# Sheet1.net
KiCad netlist of a schematic drawn in Altium Designer
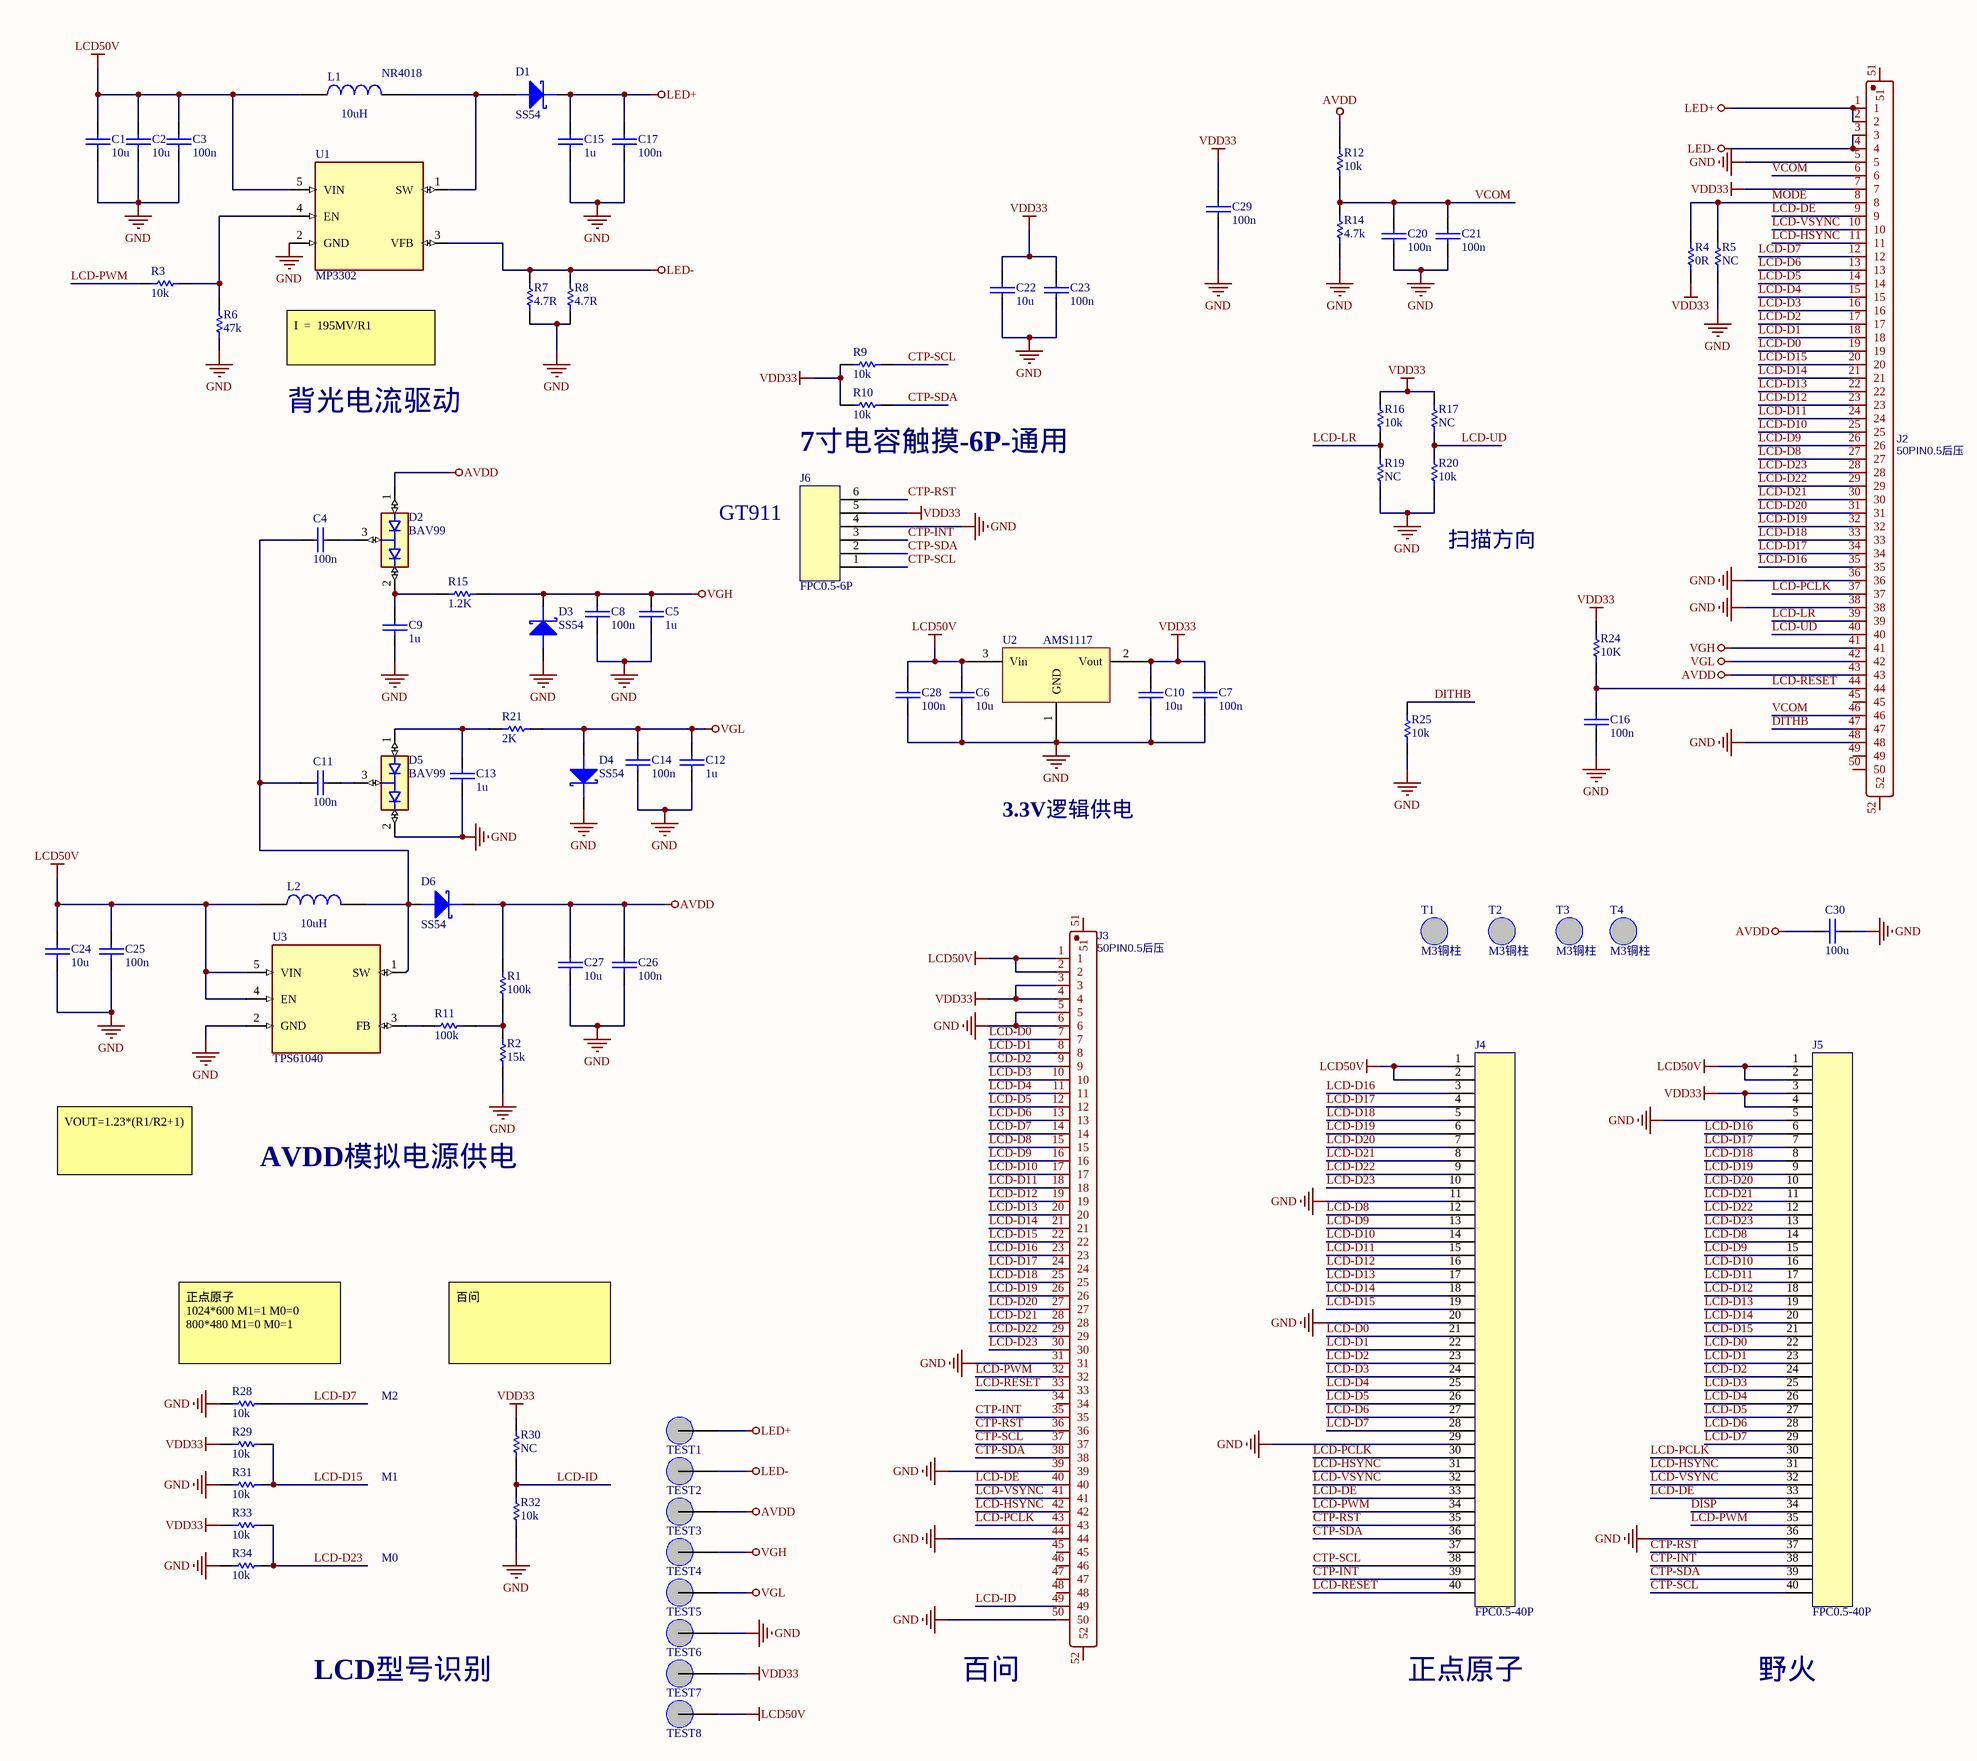
[diagram p0: Sheet1.SchDoc]

(export (version "E")
  (design (tool "Eeschema 10.0.6"))
  (components
    (comp (ref "C1")
      (value "10u")
      (footprint "0603C")
      (description "无极性电容")
      (libsource (lib "常用元件-电容") (part "CAP"))
    )
    (comp (ref "C2")
      (value "10u")
      (footprint "0603C")
      (description "无极性电容")
      (libsource (lib "常用元件-电容") (part "CAP"))
    )
    (comp (ref "C3")
      (value "100n")
      (footprint "0603C")
      (description "无极性电容")
      (libsource (lib "常用元件-电容") (part "CAP"))
    )
    (comp (ref "C4")
      (value "100n")
      (footprint "0603C")
      (description "无极性电容")
      (libsource (lib "常用元件-电容") (part "CAP"))
    )
    (comp (ref "C5")
      (value "1u")
      (footprint "0603C")
      (description "无极性电容")
      (libsource (lib "常用元件-电容") (part "CAP"))
    )
    (comp (ref "C6")
      (value "10u")
      (footprint "0603C")
      (description "无极性电容")
      (libsource (lib "常用元件-电容") (part "CAP"))
    )
    (comp (ref "C7")
      (value "100n")
      (footprint "0603C")
      (description "无极性电容")
      (libsource (lib "常用元件-电容") (part "CAP"))
    )
    (comp (ref "C8")
      (value "100n")
      (footprint "0603C")
      (description "无极性电容")
      (libsource (lib "常用元件-电容") (part "CAP"))
    )
    (comp (ref "C9")
      (value "1u")
      (footprint "0603C")
      (description "无极性电容")
      (libsource (lib "常用元件-电容") (part "CAP"))
    )
    (comp (ref "C10")
      (value "10u")
      (footprint "0603C")
      (description "无极性电容")
      (libsource (lib "常用元件-电容") (part "CAP"))
    )
    (comp (ref "C11")
      (value "100n")
      (footprint "0603C")
      (description "无极性电容")
      (libsource (lib "常用元件-电容") (part "CAP"))
    )
    (comp (ref "C12")
      (value "1u")
      (footprint "0603C")
      (description "无极性电容")
      (libsource (lib "常用元件-电容") (part "CAP"))
    )
    (comp (ref "C13")
      (value "1u")
      (footprint "0603C")
      (description "无极性电容")
      (libsource (lib "常用元件-电容") (part "CAP"))
    )
    (comp (ref "C14")
      (value "100n")
      (footprint "0603C")
      (description "无极性电容")
      (libsource (lib "常用元件-电容") (part "CAP"))
    )
    (comp (ref "C15")
      (value "1u")
      (footprint "0603C")
      (description "无极性电容")
      (libsource (lib "常用元件-电容") (part "CAP"))
    )
    (comp (ref "C16")
      (value "100n")
      (footprint "0603C")
      (description "无极性电容")
      (libsource (lib "常用元件-电容") (part "CAP"))
    )
    (comp (ref "C17")
      (value "100n")
      (footprint "0603C")
      (description "无极性电容")
      (libsource (lib "常用元件-电容") (part "CAP"))
    )
    (comp (ref "C20")
      (value "100n")
      (footprint "0603C")
      (description "无极性电容")
      (libsource (lib "常用元件-电容") (part "CAP"))
    )
    (comp (ref "C21")
      (value "100n")
      (footprint "0603C")
      (description "无极性电容")
      (libsource (lib "常用元件-电容") (part "CAP"))
    )
    (comp (ref "C22")
      (value "10u")
      (footprint "0603C")
      (description "无极性电容")
      (libsource (lib "常用元件-电容") (part "CAP"))
    )
    (comp (ref "C23")
      (value "100n")
      (footprint "0603C")
      (description "无极性电容")
      (libsource (lib "常用元件-电容") (part "CAP"))
    )
    (comp (ref "C24")
      (value "10u")
      (footprint "0603C")
      (description "无极性电容")
      (libsource (lib "常用元件-电容") (part "CAP"))
    )
    (comp (ref "C25")
      (value "100n")
      (footprint "0603C")
      (description "无极性电容")
      (libsource (lib "常用元件-电容") (part "CAP"))
    )
    (comp (ref "C26")
      (value "100n")
      (footprint "0603C")
      (description "无极性电容")
      (libsource (lib "常用元件-电容") (part "CAP"))
    )
    (comp (ref "C27")
      (value "10u")
      (footprint "0603C")
      (description "无极性电容")
      (libsource (lib "常用元件-电容") (part "CAP"))
    )
    (comp (ref "C28")
      (value "100n")
      (footprint "0603C")
      (description "无极性电容")
      (libsource (lib "常用元件-电容") (part "CAP"))
    )
    (comp (ref "C29")
      (value "100n")
      (footprint "0603C")
      (description "无极性电容")
      (libsource (lib "常用元件-电容") (part "CAP"))
    )
    (comp (ref "C30")
      (value "100u")
      (footprint "0603C")
      (description "无极性电容")
      (libsource (lib "常用元件-电容") (part "CAP"))
    )
    (comp (ref "D1")
      (value "SS54")
      (footprint "SOD-123")
      (description "肖特基二极管")
      (libsource (lib "常用元件-二极管") (part "DIODE SCHOTTKY"))
    )
    (comp (ref "D2")
      (value "BAV99")
      (footprint "BAV99:SOT23-3")
      (fields (field (name "MF") "{'manufacturer': u'ON Semiconductor'}"))
      (libsource (lib "*") (part "BAV99"))
    )
    (comp (ref "D3")
      (value "SS54")
      (footprint "SOD-123")
      (description "肖特基二极管")
      (libsource (lib "常用元件-二极管") (part "DIODE SCHOTTKY"))
    )
    (comp (ref "D4")
      (value "SS54")
      (footprint "SOD-123")
      (description "肖特基二极管")
      (libsource (lib "常用元件-二极管") (part "DIODE SCHOTTKY"))
    )
    (comp (ref "D5")
      (value "BAV99")
      (footprint "BAV99:SOT23-3")
      (fields (field (name "MF") "{'manufacturer': u'ON Semiconductor'}"))
      (libsource (lib "*") (part "BAV99"))
    )
    (comp (ref "D6")
      (value "SS54")
      (footprint "SOD-123")
      (description "肖特基二极管")
      (libsource (lib "常用元件-二极管") (part "DIODE SCHOTTKY"))
    )
    (comp (ref "J2")
      (value "50PIN0.5后压")
      (footprint "FPC-SMD_KH-FG0.5-H2.0-50PIN")
      (fields (field (name "BOM_SUPPLIER PART") "C9900011403") (field (name "CONTRIBUTOR") "LCSC"))
      (libsource (lib "altium-import") (part "root_0_50PIN0.5后压_"))
    )
    (comp (ref "J3")
      (value "50PIN0.5后压")
      (footprint "FPC-SMD_KH-FG0.5-H2.0-50PIN")
      (fields (field (name "BOM_SUPPLIER PART") "C9900011403") (field (name "CONTRIBUTOR") "LCSC"))
      (libsource (lib "altium-import") (part "root_0_50PIN0.5后压_"))
    )
    (comp (ref "J4")
      (value "FPC0.5-40P")
      (footprint "FPC0.5-40P")
      (description "贴片")
      (libsource (lib "插接类-FPC") (part "FPC0.5-40P"))
    )
    (comp (ref "J5")
      (value "FPC0.5-40P")
      (footprint "FPC0.5-40P")
      (description "贴片")
      (libsource (lib "插接类-FPC") (part "FPC0.5-40P"))
    )
    (comp (ref "J6")
      (value "FPC0.5-6P")
      (footprint "FPC0.5-6P")
      (description "贴片")
      (libsource (lib "插接类-FPC") (part "FPC0.5-6P"))
    )
    (comp (ref "L1")
      (value "10uH")
      (footprint "CD42")
      (description "INDUCTOR")
      (libsource (lib "常用元件-电感") (part "INDUCTOR"))
    )
    (comp (ref "L2")
      (value "10uH")
      (footprint "CD42")
      (description "INDUCTOR")
      (libsource (lib "常用元件-电感") (part "INDUCTOR"))
    )
    (comp (ref "R1") (value "100k") (footprint "0603R") (libsource (lib "常用元件-电阻") (part "RES")))
    (comp (ref "R2") (value "15k") (footprint "0603R") (libsource (lib "常用元件-电阻") (part "RES")))
    (comp (ref "R3") (value "10k") (footprint "0603R") (libsource (lib "常用元件-电阻") (part "RES")))
    (comp (ref "R4") (value "0R") (footprint "0603R") (libsource (lib "常用元件-电阻") (part "RES")))
    (comp (ref "R5") (value "NC") (footprint "0603R") (libsource (lib "常用元件-电阻") (part "RES")))
    (comp (ref "R6") (value "47k") (footprint "0603R") (libsource (lib "常用元件-电阻") (part "RES")))
    (comp (ref "R7") (value "4.7R") (footprint "0603R") (libsource (lib "常用元件-电阻") (part "RES")))
    (comp (ref "R8") (value "4.7R") (footprint "0603R") (libsource (lib "常用元件-电阻") (part "RES")))
    (comp (ref "R9") (value "10k") (footprint "0603R") (libsource (lib "常用元件-电阻") (part "RES")))
    (comp (ref "R10") (value "10k") (footprint "0603R") (libsource (lib "常用元件-电阻") (part "RES")))
    (comp (ref "R11") (value "100k") (footprint "0603R") (libsource (lib "常用元件-电阻") (part "RES")))
    (comp (ref "R12") (value "10k") (footprint "0603R") (libsource (lib "常用元件-电阻") (part "RES")))
    (comp (ref "R14") (value "4.7k") (footprint "0603R") (libsource (lib "常用元件-电阻") (part "RES")))
    (comp (ref "R15") (value "1.2K") (footprint "0603R") (libsource (lib "常用元件-电阻") (part "RES")))
    (comp (ref "R16") (value "10k") (footprint "0603R") (libsource (lib "常用元件-电阻") (part "RES")))
    (comp (ref "R17") (value "NC") (footprint "0603R") (libsource (lib "常用元件-电阻") (part "RES")))
    (comp (ref "R19") (value "NC") (footprint "0603R") (libsource (lib "常用元件-电阻") (part "RES")))
    (comp (ref "R20") (value "10k") (footprint "0603R") (libsource (lib "常用元件-电阻") (part "RES")))
    (comp (ref "R21") (value "2K") (footprint "0603R") (libsource (lib "常用元件-电阻") (part "RES")))
    (comp (ref "R24") (value "10K") (footprint "0603R") (libsource (lib "常用元件-电阻") (part "RES")))
    (comp (ref "R25") (value "10k") (footprint "0603R") (libsource (lib "常用元件-电阻") (part "RES")))
    (comp (ref "R28") (value "10k") (footprint "0603R") (libsource (lib "常用元件-电阻") (part "RES")))
    (comp (ref "R29") (value "10k") (footprint "0603R") (libsource (lib "常用元件-电阻") (part "RES")))
    (comp (ref "R30") (value "NC") (footprint "0603R") (libsource (lib "常用元件-电阻") (part "RES")))
    (comp (ref "R31") (value "10k") (footprint "0603R") (libsource (lib "常用元件-电阻") (part "RES")))
    (comp (ref "R32") (value "10k") (footprint "0603R") (libsource (lib "常用元件-电阻") (part "RES")))
    (comp (ref "R33") (value "10k") (footprint "0603R") (libsource (lib "常用元件-电阻") (part "RES")))
    (comp (ref "R34") (value "10k") (footprint "0603R") (libsource (lib "常用元件-电阻") (part "RES")))
    (comp (ref "T1") (value "M3铜柱") (footprint "M3 单孔") (libsource (lib "M3铜柱") (part "M3铜柱")))
    (comp (ref "T2") (value "M3铜柱") (footprint "M3 单孔") (libsource (lib "M3铜柱") (part "M3铜柱")))
    (comp (ref "T3") (value "M3铜柱") (footprint "M3 单孔") (libsource (lib "M3铜柱") (part "M3铜柱")))
    (comp (ref "T4") (value "M3铜柱") (footprint "M3 单孔") (libsource (lib "M3铜柱") (part "M3铜柱")))
    (comp (ref "TEST1")
      (value "TEST")
      (footprint "TEST SMALL")
      (description "测试针")
      (fields (field (name "版权归属") "源创客"))
      (libsource (lib "测试类-测试针") (part "TEST"))
    )
    (comp (ref "TEST2")
      (value "TEST")
      (footprint "TEST SMALL")
      (description "测试针")
      (fields (field (name "版权归属") "源创客"))
      (libsource (lib "测试类-测试针") (part "TEST"))
    )
    (comp (ref "TEST3")
      (value "TEST")
      (footprint "TEST SMALL")
      (description "测试针")
      (fields (field (name "版权归属") "源创客"))
      (libsource (lib "测试类-测试针") (part "TEST"))
    )
    (comp (ref "TEST4")
      (value "TEST")
      (footprint "TEST SMALL")
      (description "测试针")
      (fields (field (name "版权归属") "源创客"))
      (libsource (lib "测试类-测试针") (part "TEST"))
    )
    (comp (ref "TEST5")
      (value "TEST")
      (footprint "TEST SMALL")
      (description "测试针")
      (fields (field (name "版权归属") "源创客"))
      (libsource (lib "测试类-测试针") (part "TEST"))
    )
    (comp (ref "TEST6")
      (value "TEST")
      (footprint "TEST SMALL")
      (description "测试针")
      (fields (field (name "版权归属") "源创客"))
      (libsource (lib "测试类-测试针") (part "TEST"))
    )
    (comp (ref "TEST7")
      (value "TEST")
      (footprint "TEST SMALL")
      (description "测试针")
      (fields (field (name "版权归属") "源创客"))
      (libsource (lib "测试类-测试针") (part "TEST"))
    )
    (comp (ref "TEST8")
      (value "TEST")
      (footprint "TEST SMALL")
      (description "测试针")
      (fields (field (name "版权归属") "源创客"))
      (libsource (lib "测试类-测试针") (part "TEST"))
    )
    (comp (ref "U1")
      (value "MP3302")
      (footprint "SOT95P280X100-5N")
      (fields
        (field (name "MP") "TPS563201DDCR")
        (field (name "MF") "{'manufacturer': u'Texas Instruments'}")
      )
      (libsource (lib "MP3302") (part "MP3302"))
    )
    (comp (ref "U2")
      (value "AMS1117")
      (footprint "SOT223")
      (description "三端稳压芯片")
      (libsource (lib "芯片-电源芯片") (part "AMS1117"))
    )
    (comp (ref "U3")
      (value "TPS61040")
      (footprint "SOT95P280X100-5N")
      (fields
        (field (name "MP") "TPS563201DDCR")
        (field (name "MF") "{'manufacturer': u'Texas Instruments'}")
      )
      (libsource (lib "MP1541") (part "MP1541"))
    )
  )
  (nets
    (net (code "1") (name "/CTP-INT") (class "Default")
      (node (ref "J3") (pin "35") (pinfunction "35_35") (pintype "passive"))
      (node (ref "J4") (pin "39") (pinfunction "39_39") (pintype "passive"))
      (node (ref "J5") (pin "38") (pinfunction "38_38") (pintype "passive"))
      (node (ref "J6") (pin "3") (pinfunction "3_3") (pintype "passive"))
    )
    (net (code "2") (name "/CTP-RST") (class "Default")
      (node (ref "J3") (pin "36") (pinfunction "36_36") (pintype "passive"))
      (node (ref "J4") (pin "35") (pinfunction "35_35") (pintype "passive"))
      (node (ref "J5") (pin "37") (pinfunction "37_37") (pintype "passive"))
      (node (ref "J6") (pin "6") (pinfunction "6_6") (pintype "passive"))
    )
    (net (code "3") (name "/CTP-SCL") (class "Default")
      (node (ref "J3") (pin "37") (pinfunction "37_37") (pintype "passive"))
      (node (ref "J4") (pin "38") (pinfunction "38_38") (pintype "passive"))
      (node (ref "J5") (pin "40") (pinfunction "40_40") (pintype "passive"))
      (node (ref "J6") (pin "1") (pinfunction "1_1") (pintype "passive"))
      (node (ref "R9") (pin "1") (pinfunction "1_1") (pintype "passive"))
    )
    (net (code "4") (name "/CTP-SDA") (class "Default")
      (node (ref "J3") (pin "38") (pinfunction "38_38") (pintype "passive"))
      (node (ref "J4") (pin "36") (pinfunction "36_36") (pintype "passive"))
      (node (ref "J5") (pin "39") (pinfunction "39_39") (pintype "passive"))
      (node (ref "J6") (pin "2") (pinfunction "2_2") (pintype "passive"))
      (node (ref "R10") (pin "1") (pinfunction "1_1") (pintype "passive"))
    )
    (net (code "5") (name "/DISP") (class "Default")
      (node (ref "J5") (pin "34") (pinfunction "34_34") (pintype "passive"))
    )
    (net (code "6") (name "/DITHB") (class "Default")
      (node (ref "J2") (pin "47") (pinfunction "47_47") (pintype "passive"))
      (node (ref "R25") (pin "1") (pinfunction "1_1") (pintype "passive"))
    )
    (net (code "7") (name "/LCD-D0") (class "Default")
      (node (ref "J2") (pin "19") (pinfunction "19_19") (pintype "passive"))
      (node (ref "J3") (pin "7") (pinfunction "7_7") (pintype "passive"))
      (node (ref "J4") (pin "21") (pinfunction "21_21") (pintype "passive"))
      (node (ref "J5") (pin "22") (pinfunction "22_22") (pintype "passive"))
    )
    (net (code "8") (name "/LCD-D1") (class "Default")
      (node (ref "J2") (pin "18") (pinfunction "18_18") (pintype "passive"))
      (node (ref "J3") (pin "8") (pinfunction "8_8") (pintype "passive"))
      (node (ref "J4") (pin "22") (pinfunction "22_22") (pintype "passive"))
      (node (ref "J5") (pin "23") (pinfunction "23_23") (pintype "passive"))
    )
    (net (code "9") (name "/LCD-D2") (class "Default")
      (node (ref "J2") (pin "17") (pinfunction "17_17") (pintype "passive"))
      (node (ref "J3") (pin "9") (pinfunction "9_9") (pintype "passive"))
      (node (ref "J4") (pin "23") (pinfunction "23_23") (pintype "passive"))
      (node (ref "J5") (pin "24") (pinfunction "24_24") (pintype "passive"))
    )
    (net (code "10") (name "/LCD-D3") (class "Default")
      (node (ref "J2") (pin "16") (pinfunction "16_16") (pintype "passive"))
      (node (ref "J3") (pin "10") (pinfunction "10_10") (pintype "passive"))
      (node (ref "J4") (pin "24") (pinfunction "24_24") (pintype "passive"))
      (node (ref "J5") (pin "25") (pinfunction "25_25") (pintype "passive"))
    )
    (net (code "11") (name "/LCD-D4") (class "Default")
      (node (ref "J2") (pin "15") (pinfunction "15_15") (pintype "passive"))
      (node (ref "J3") (pin "11") (pinfunction "11_11") (pintype "passive"))
      (node (ref "J4") (pin "25") (pinfunction "25_25") (pintype "passive"))
      (node (ref "J5") (pin "26") (pinfunction "26_26") (pintype "passive"))
    )
    (net (code "12") (name "/LCD-D5") (class "Default")
      (node (ref "J2") (pin "14") (pinfunction "14_14") (pintype "passive"))
      (node (ref "J3") (pin "12") (pinfunction "12_12") (pintype "passive"))
      (node (ref "J4") (pin "26") (pinfunction "26_26") (pintype "passive"))
      (node (ref "J5") (pin "27") (pinfunction "27_27") (pintype "passive"))
    )
    (net (code "13") (name "/LCD-D6") (class "Default")
      (node (ref "J2") (pin "13") (pinfunction "13_13") (pintype "passive"))
      (node (ref "J3") (pin "13") (pinfunction "13_13") (pintype "passive"))
      (node (ref "J4") (pin "27") (pinfunction "27_27") (pintype "passive"))
      (node (ref "J5") (pin "28") (pinfunction "28_28") (pintype "passive"))
    )
    (net (code "14") (name "/LCD-D7") (class "Default")
      (node (ref "J2") (pin "12") (pinfunction "12_12") (pintype "passive"))
      (node (ref "J3") (pin "14") (pinfunction "14_14") (pintype "passive"))
      (node (ref "J4") (pin "28") (pinfunction "28_28") (pintype "passive"))
      (node (ref "J5") (pin "29") (pinfunction "29_29") (pintype "passive"))
      (node (ref "R28") (pin "2") (pinfunction "2_2") (pintype "passive"))
    )
    (net (code "15") (name "/LCD-D8") (class "Default")
      (node (ref "J2") (pin "27") (pinfunction "27_27") (pintype "passive"))
      (node (ref "J3") (pin "15") (pinfunction "15_15") (pintype "passive"))
      (node (ref "J4") (pin "12") (pinfunction "12_12") (pintype "passive"))
      (node (ref "J5") (pin "14") (pinfunction "14_14") (pintype "passive"))
    )
    (net (code "16") (name "/LCD-D9") (class "Default")
      (node (ref "J2") (pin "26") (pinfunction "26_26") (pintype "passive"))
      (node (ref "J3") (pin "16") (pinfunction "16_16") (pintype "passive"))
      (node (ref "J4") (pin "13") (pinfunction "13_13") (pintype "passive"))
      (node (ref "J5") (pin "15") (pinfunction "15_15") (pintype "passive"))
    )
    (net (code "17") (name "/LCD-D10") (class "Default")
      (node (ref "J2") (pin "25") (pinfunction "25_25") (pintype "passive"))
      (node (ref "J3") (pin "17") (pinfunction "17_17") (pintype "passive"))
      (node (ref "J4") (pin "14") (pinfunction "14_14") (pintype "passive"))
      (node (ref "J5") (pin "16") (pinfunction "16_16") (pintype "passive"))
    )
    (net (code "18") (name "/LCD-D11") (class "Default")
      (node (ref "J2") (pin "24") (pinfunction "24_24") (pintype "passive"))
      (node (ref "J3") (pin "18") (pinfunction "18_18") (pintype "passive"))
      (node (ref "J4") (pin "15") (pinfunction "15_15") (pintype "passive"))
      (node (ref "J5") (pin "17") (pinfunction "17_17") (pintype "passive"))
    )
    (net (code "19") (name "/LCD-D12") (class "Default")
      (node (ref "J2") (pin "23") (pinfunction "23_23") (pintype "passive"))
      (node (ref "J3") (pin "19") (pinfunction "19_19") (pintype "passive"))
      (node (ref "J4") (pin "16") (pinfunction "16_16") (pintype "passive"))
      (node (ref "J5") (pin "18") (pinfunction "18_18") (pintype "passive"))
    )
    (net (code "20") (name "/LCD-D13") (class "Default")
      (node (ref "J2") (pin "22") (pinfunction "22_22") (pintype "passive"))
      (node (ref "J3") (pin "20") (pinfunction "20_20") (pintype "passive"))
      (node (ref "J4") (pin "17") (pinfunction "17_17") (pintype "passive"))
      (node (ref "J5") (pin "19") (pinfunction "19_19") (pintype "passive"))
    )
    (net (code "21") (name "/LCD-D14") (class "Default")
      (node (ref "J2") (pin "21") (pinfunction "21_21") (pintype "passive"))
      (node (ref "J3") (pin "21") (pinfunction "21_21") (pintype "passive"))
      (node (ref "J4") (pin "18") (pinfunction "18_18") (pintype "passive"))
      (node (ref "J5") (pin "20") (pinfunction "20_20") (pintype "passive"))
    )
    (net (code "22") (name "/LCD-D15") (class "Default")
      (node (ref "J2") (pin "20") (pinfunction "20_20") (pintype "passive"))
      (node (ref "J3") (pin "22") (pinfunction "22_22") (pintype "passive"))
      (node (ref "J4") (pin "19") (pinfunction "19_19") (pintype "passive"))
      (node (ref "J5") (pin "21") (pinfunction "21_21") (pintype "passive"))
      (node (ref "R29") (pin "2") (pinfunction "2_2") (pintype "passive"))
      (node (ref "R31") (pin "1") (pinfunction "1_1") (pintype "passive"))
    )
    (net (code "23") (name "/LCD-D16") (class "Default")
      (node (ref "J2") (pin "35") (pinfunction "35_35") (pintype "passive"))
      (node (ref "J3") (pin "23") (pinfunction "23_23") (pintype "passive"))
      (node (ref "J4") (pin "3") (pinfunction "3_3") (pintype "passive"))
      (node (ref "J5") (pin "6") (pinfunction "6_6") (pintype "passive"))
    )
    (net (code "24") (name "/LCD-D17") (class "Default")
      (node (ref "J2") (pin "34") (pinfunction "34_34") (pintype "passive"))
      (node (ref "J3") (pin "24") (pinfunction "24_24") (pintype "passive"))
      (node (ref "J4") (pin "4") (pinfunction "4_4") (pintype "passive"))
      (node (ref "J5") (pin "7") (pinfunction "7_7") (pintype "passive"))
    )
    (net (code "25") (name "/LCD-D18") (class "Default")
      (node (ref "J2") (pin "33") (pinfunction "33_33") (pintype "passive"))
      (node (ref "J3") (pin "25") (pinfunction "25_25") (pintype "passive"))
      (node (ref "J4") (pin "5") (pinfunction "5_5") (pintype "passive"))
      (node (ref "J5") (pin "8") (pinfunction "8_8") (pintype "passive"))
    )
    (net (code "26") (name "/LCD-D19") (class "Default")
      (node (ref "J2") (pin "32") (pinfunction "32_32") (pintype "passive"))
      (node (ref "J3") (pin "26") (pinfunction "26_26") (pintype "passive"))
      (node (ref "J4") (pin "6") (pinfunction "6_6") (pintype "passive"))
      (node (ref "J5") (pin "9") (pinfunction "9_9") (pintype "passive"))
    )
    (net (code "27") (name "/LCD-D20") (class "Default")
      (node (ref "J2") (pin "31") (pinfunction "31_31") (pintype "passive"))
      (node (ref "J3") (pin "27") (pinfunction "27_27") (pintype "passive"))
      (node (ref "J4") (pin "7") (pinfunction "7_7") (pintype "passive"))
      (node (ref "J5") (pin "10") (pinfunction "10_10") (pintype "passive"))
    )
    (net (code "28") (name "/LCD-D21") (class "Default")
      (node (ref "J2") (pin "30") (pinfunction "30_30") (pintype "passive"))
      (node (ref "J3") (pin "28") (pinfunction "28_28") (pintype "passive"))
      (node (ref "J4") (pin "8") (pinfunction "8_8") (pintype "passive"))
      (node (ref "J5") (pin "11") (pinfunction "11_11") (pintype "passive"))
    )
    (net (code "29") (name "/LCD-D22") (class "Default")
      (node (ref "J2") (pin "29") (pinfunction "29_29") (pintype "passive"))
      (node (ref "J3") (pin "29") (pinfunction "29_29") (pintype "passive"))
      (node (ref "J4") (pin "9") (pinfunction "9_9") (pintype "passive"))
      (node (ref "J5") (pin "12") (pinfunction "12_12") (pintype "passive"))
    )
    (net (code "30") (name "/LCD-D23") (class "Default")
      (node (ref "J2") (pin "28") (pinfunction "28_28") (pintype "passive"))
      (node (ref "J3") (pin "30") (pinfunction "30_30") (pintype "passive"))
      (node (ref "J4") (pin "10") (pinfunction "10_10") (pintype "passive"))
      (node (ref "J5") (pin "13") (pinfunction "13_13") (pintype "passive"))
      (node (ref "R33") (pin "2") (pinfunction "2_2") (pintype "passive"))
      (node (ref "R34") (pin "1") (pinfunction "1_1") (pintype "passive"))
    )
    (net (code "31") (name "/LCD-DE") (class "Default")
      (node (ref "J2") (pin "9") (pinfunction "9_9") (pintype "passive"))
      (node (ref "J3") (pin "40") (pinfunction "40_40") (pintype "passive"))
      (node (ref "J4") (pin "33") (pinfunction "33_33") (pintype "passive"))
      (node (ref "J5") (pin "33") (pinfunction "33_33") (pintype "passive"))
    )
    (net (code "32") (name "/LCD-HSYNC") (class "Default")
      (node (ref "J2") (pin "11") (pinfunction "11_11") (pintype "passive"))
      (node (ref "J3") (pin "42") (pinfunction "42_42") (pintype "passive"))
      (node (ref "J4") (pin "31") (pinfunction "31_31") (pintype "passive"))
      (node (ref "J5") (pin "31") (pinfunction "31_31") (pintype "passive"))
    )
    (net (code "33") (name "/LCD-ID") (class "Default")
      (node (ref "J3") (pin "49") (pinfunction "49_49") (pintype "passive"))
      (node (ref "R30") (pin "2") (pinfunction "2_2") (pintype "passive"))
      (node (ref "R32") (pin "2") (pinfunction "2_2") (pintype "passive"))
    )
    (net (code "34") (name "/LCD-LR") (class "Default")
      (node (ref "J2") (pin "39") (pinfunction "39_39") (pintype "passive"))
      (node (ref "R16") (pin "2") (pinfunction "2_2") (pintype "passive"))
      (node (ref "R19") (pin "1") (pinfunction "1_1") (pintype "passive"))
    )
    (net (code "35") (name "/LCD-PCLK") (class "Default")
      (node (ref "J2") (pin "37") (pinfunction "37_37") (pintype "passive"))
      (node (ref "J3") (pin "43") (pinfunction "43_43") (pintype "passive"))
      (node (ref "J4") (pin "30") (pinfunction "30_30") (pintype "passive"))
      (node (ref "J5") (pin "30") (pinfunction "30_30") (pintype "passive"))
    )
    (net (code "36") (name "/LCD-PWM") (class "Default")
      (node (ref "J3") (pin "32") (pinfunction "32_32") (pintype "passive"))
      (node (ref "J4") (pin "34") (pinfunction "34_34") (pintype "passive"))
      (node (ref "J5") (pin "35") (pinfunction "35_35") (pintype "passive"))
      (node (ref "R3") (pin "1") (pinfunction "1_1") (pintype "passive"))
    )
    (net (code "37") (name "/LCD-RESET") (class "Default")
      (node (ref "C16") (pin "2") (pinfunction "2_2") (pintype "passive"))
      (node (ref "J2") (pin "44") (pinfunction "44_44") (pintype "passive"))
      (node (ref "J3") (pin "33") (pinfunction "33_33") (pintype "passive"))
      (node (ref "J4") (pin "40") (pinfunction "40_40") (pintype "passive"))
      (node (ref "R24") (pin "2") (pinfunction "2_2") (pintype "passive"))
    )
    (net (code "38") (name "/LCD-UD") (class "Default")
      (node (ref "J2") (pin "40") (pinfunction "40_40") (pintype "passive"))
      (node (ref "R17") (pin "2") (pinfunction "2_2") (pintype "passive"))
      (node (ref "R20") (pin "1") (pinfunction "1_1") (pintype "passive"))
    )
    (net (code "39") (name "/LCD-VSYNC") (class "Default")
      (node (ref "J2") (pin "10") (pinfunction "10_10") (pintype "passive"))
      (node (ref "J3") (pin "41") (pinfunction "41_41") (pintype "passive"))
      (node (ref "J4") (pin "32") (pinfunction "32_32") (pintype "passive"))
      (node (ref "J5") (pin "32") (pinfunction "32_32") (pintype "passive"))
    )
    (net (code "40") (name "/MODE") (class "Default")
      (node (ref "J2") (pin "8") (pinfunction "8_8") (pintype "passive"))
      (node (ref "R4") (pin "1") (pinfunction "1_1") (pintype "passive"))
      (node (ref "R5") (pin "1") (pinfunction "1_1") (pintype "passive"))
    )
    (net (code "41") (name "/VCOM") (class "Default")
      (node (ref "C20") (pin "2") (pinfunction "2_2") (pintype "passive"))
      (node (ref "C21") (pin "2") (pinfunction "2_2") (pintype "passive"))
      (node (ref "J2") (pin "46") (pinfunction "46_46") (pintype "passive"))
      (node (ref "J2") (pin "6") (pinfunction "6_6") (pintype "passive"))
      (node (ref "R12") (pin "2") (pinfunction "2_2") (pintype "passive"))
      (node (ref "R14") (pin "1") (pinfunction "1_1") (pintype "passive"))
    )
    (net (code "42") (name "AVDD") (class "Default")
      (node (ref "C26") (pin "2") (pinfunction "2_2") (pintype "passive"))
      (node (ref "C27") (pin "2") (pinfunction "2_2") (pintype "passive"))
      (node (ref "C30") (pin "1") (pinfunction "1_1") (pintype "passive"))
      (node (ref "D2") (pin "1") (pinfunction "A1_1") (pintype "bidirectional"))
      (node (ref "D6") (pin "K") (pinfunction "K_K") (pintype "passive"))
      (node (ref "J2") (pin "43") (pinfunction "43_43") (pintype "passive"))
      (node (ref "R1") (pin "1") (pinfunction "1_1") (pintype "passive"))
      (node (ref "R12") (pin "1") (pinfunction "1_1") (pintype "passive"))
      (node (ref "TEST3") (pin "1") (pinfunction "1_1") (pintype "passive"))
    )
    (net (code "43") (name "GND") (class "Default")
      (node (ref "C1") (pin "1") (pinfunction "1_1") (pintype "passive"))
      (node (ref "C10") (pin "1") (pinfunction "1_1") (pintype "passive"))
      (node (ref "C12") (pin "1") (pinfunction "1_1") (pintype "passive"))
      (node (ref "C13") (pin "2") (pinfunction "2_2") (pintype "passive"))
      (node (ref "C14") (pin "1") (pinfunction "1_1") (pintype "passive"))
      (node (ref "C15") (pin "1") (pinfunction "1_1") (pintype "passive"))
      (node (ref "C16") (pin "1") (pinfunction "1_1") (pintype "passive"))
      (node (ref "C17") (pin "1") (pinfunction "1_1") (pintype "passive"))
      (node (ref "C2") (pin "1") (pinfunction "1_1") (pintype "passive"))
      (node (ref "C20") (pin "1") (pinfunction "1_1") (pintype "passive"))
      (node (ref "C21") (pin "1") (pinfunction "1_1") (pintype "passive"))
      (node (ref "C22") (pin "1") (pinfunction "1_1") (pintype "passive"))
      (node (ref "C23") (pin "1") (pinfunction "1_1") (pintype "passive"))
      (node (ref "C24") (pin "1") (pinfunction "1_1") (pintype "passive"))
      (node (ref "C25") (pin "1") (pinfunction "1_1") (pintype "passive"))
      (node (ref "C26") (pin "1") (pinfunction "1_1") (pintype "passive"))
      (node (ref "C27") (pin "1") (pinfunction "1_1") (pintype "passive"))
      (node (ref "C28") (pin "1") (pinfunction "1_1") (pintype "passive"))
      (node (ref "C29") (pin "1") (pinfunction "1_1") (pintype "passive"))
      (node (ref "C3") (pin "1") (pinfunction "1_1") (pintype "passive"))
      (node (ref "C30") (pin "2") (pinfunction "2_2") (pintype "passive"))
      (node (ref "C5") (pin "1") (pinfunction "1_1") (pintype "passive"))
      (node (ref "C6") (pin "1") (pinfunction "1_1") (pintype "passive"))
      (node (ref "C7") (pin "1") (pinfunction "1_1") (pintype "passive"))
      (node (ref "C8") (pin "1") (pinfunction "1_1") (pintype "passive"))
      (node (ref "C9") (pin "1") (pinfunction "1_1") (pintype "passive"))
      (node (ref "D3") (pin "A") (pinfunction "A_A") (pintype "passive"))
      (node (ref "D4") (pin "K") (pinfunction "K_K") (pintype "passive"))
      (node (ref "D5") (pin "2") (pinfunction "C2_2") (pintype "bidirectional"))
      (node (ref "J2") (pin "36") (pinfunction "36_36") (pintype "passive"))
      (node (ref "J2") (pin "38") (pinfunction "38_38") (pintype "passive"))
      (node (ref "J2") (pin "48") (pinfunction "48_48") (pintype "passive"))
      (node (ref "J2") (pin "5") (pinfunction "5_5") (pintype "passive"))
      (node (ref "J3") (pin "31") (pinfunction "31_31") (pintype "passive"))
      (node (ref "J3") (pin "39") (pinfunction "39_39") (pintype "passive"))
      (node (ref "J3") (pin "44") (pinfunction "44_44") (pintype "passive"))
      (node (ref "J3") (pin "5") (pinfunction "5_5") (pintype "passive"))
      (node (ref "J3") (pin "50") (pinfunction "50_50") (pintype "passive"))
      (node (ref "J3") (pin "6") (pinfunction "6_6") (pintype "passive"))
      (node (ref "J4") (pin "11") (pinfunction "11_11") (pintype "passive"))
      (node (ref "J4") (pin "20") (pinfunction "20_20") (pintype "passive"))
      (node (ref "J4") (pin "29") (pinfunction "29_29") (pintype "passive"))
      (node (ref "J5") (pin "36") (pinfunction "36_36") (pintype "passive"))
      (node (ref "J5") (pin "5") (pinfunction "5_5") (pintype "passive"))
      (node (ref "J6") (pin "4") (pinfunction "4_4") (pintype "passive"))
      (node (ref "R14") (pin "2") (pinfunction "2_2") (pintype "passive"))
      (node (ref "R19") (pin "2") (pinfunction "2_2") (pintype "passive"))
      (node (ref "R2") (pin "1") (pinfunction "1_1") (pintype "passive"))
      (node (ref "R20") (pin "2") (pinfunction "2_2") (pintype "passive"))
      (node (ref "R25") (pin "2") (pinfunction "2_2") (pintype "passive"))
      (node (ref "R28") (pin "1") (pinfunction "1_1") (pintype "passive"))
      (node (ref "R31") (pin "2") (pinfunction "2_2") (pintype "passive"))
      (node (ref "R32") (pin "1") (pinfunction "1_1") (pintype "passive"))
      (node (ref "R34") (pin "2") (pinfunction "2_2") (pintype "passive"))
      (node (ref "R5") (pin "2") (pinfunction "2_2") (pintype "passive"))
      (node (ref "R6") (pin "1") (pinfunction "1_1") (pintype "passive"))
      (node (ref "R7") (pin "1") (pinfunction "1_1") (pintype "passive"))
      (node (ref "R8") (pin "1") (pinfunction "1_1") (pintype "passive"))
      (node (ref "TEST6") (pin "1") (pinfunction "1_1") (pintype "passive"))
      (node (ref "U1") (pin "2") (pinfunction "GND_2") (pintype "input"))
      (node (ref "U2") (pin "1") (pinfunction "GND_1") (pintype "passive"))
      (node (ref "U3") (pin "2") (pinfunction "GND_2") (pintype "input"))
    )
    (net (code "44") (name "LCD50V") (class "Default")
      (node (ref "C1") (pin "2") (pinfunction "2_2") (pintype "passive"))
      (node (ref "C2") (pin "2") (pinfunction "2_2") (pintype "passive"))
      (node (ref "C24") (pin "2") (pinfunction "2_2") (pintype "passive"))
      (node (ref "C25") (pin "2") (pinfunction "2_2") (pintype "passive"))
      (node (ref "C28") (pin "2") (pinfunction "2_2") (pintype "passive"))
      (node (ref "C3") (pin "2") (pinfunction "2_2") (pintype "passive"))
      (node (ref "C6") (pin "2") (pinfunction "2_2") (pintype "passive"))
      (node (ref "J3") (pin "1") (pinfunction "1_1") (pintype "passive"))
      (node (ref "J3") (pin "2") (pinfunction "2_2") (pintype "passive"))
      (node (ref "J4") (pin "1") (pinfunction "1_1") (pintype "passive"))
      (node (ref "J4") (pin "2") (pinfunction "2_2") (pintype "passive"))
      (node (ref "J5") (pin "1") (pinfunction "1_1") (pintype "passive"))
      (node (ref "J5") (pin "2") (pinfunction "2_2") (pintype "passive"))
      (node (ref "L1") (pin "1") (pinfunction "1_1") (pintype "passive"))
      (node (ref "L2") (pin "1") (pinfunction "1_1") (pintype "passive"))
      (node (ref "TEST8") (pin "1") (pinfunction "1_1") (pintype "passive"))
      (node (ref "U1") (pin "5") (pinfunction "VIN_5") (pintype "input"))
      (node (ref "U2") (pin "3") (pinfunction "Vin_3") (pintype "passive"))
      (node (ref "U3") (pin "4") (pinfunction "EN_4") (pintype "input"))
      (node (ref "U3") (pin "5") (pinfunction "VIN_5") (pintype "input"))
    )
    (net (code "45") (name "LED+") (class "Default")
      (node (ref "C15") (pin "2") (pinfunction "2_2") (pintype "passive"))
      (node (ref "C17") (pin "2") (pinfunction "2_2") (pintype "passive"))
      (node (ref "D1") (pin "K") (pinfunction "K_K") (pintype "passive"))
      (node (ref "J2") (pin "1") (pinfunction "1_1") (pintype "passive"))
      (node (ref "J2") (pin "2") (pinfunction "2_2") (pintype "passive"))
      (node (ref "TEST1") (pin "1") (pinfunction "1_1") (pintype "passive"))
    )
    (net (code "46") (name "LED-") (class "Default")
      (node (ref "J2") (pin "3") (pinfunction "3_3") (pintype "passive"))
      (node (ref "J2") (pin "4") (pinfunction "4_4") (pintype "passive"))
      (node (ref "R7") (pin "2") (pinfunction "2_2") (pintype "passive"))
      (node (ref "R8") (pin "2") (pinfunction "2_2") (pintype "passive"))
      (node (ref "TEST2") (pin "1") (pinfunction "1_1") (pintype "passive"))
      (node (ref "U1") (pin "3") (pinfunction "VFB_3") (pintype "bidirectional"))
    )
    (net (code "47") (name "Net-(D2-C2)") (class "Default")
      (node (ref "C9") (pin "2") (pinfunction "2_2") (pintype "passive"))
      (node (ref "D2") (pin "2") (pinfunction "C2_2") (pintype "bidirectional"))
      (node (ref "R15") (pin "1") (pinfunction "1_1") (pintype "passive"))
    )
    (net (code "48") (name "Net-(D2-COM)") (class "Default")
      (node (ref "C4") (pin "1") (pinfunction "1_1") (pintype "passive"))
      (node (ref "D2") (pin "3") (pinfunction "COM_3") (pintype "bidirectional"))
    )
    (net (code "49") (name "Net-(D5-A1)") (class "Default")
      (node (ref "C13") (pin "1") (pinfunction "1_1") (pintype "passive"))
      (node (ref "D5") (pin "1") (pinfunction "A1_1") (pintype "bidirectional"))
      (node (ref "R21") (pin "1") (pinfunction "1_1") (pintype "passive"))
    )
    (net (code "50") (name "Net-(D5-COM)") (class "Default")
      (node (ref "C11") (pin "1") (pinfunction "1_1") (pintype "passive"))
      (node (ref "D5") (pin "3") (pinfunction "COM_3") (pintype "bidirectional"))
    )
    (net (code "51") (name "Net-(R1-Pad2)") (class "Default")
      (node (ref "R1") (pin "2") (pinfunction "2_2") (pintype "passive"))
      (node (ref "R11") (pin "2") (pinfunction "2_2") (pintype "passive"))
      (node (ref "R2") (pin "2") (pinfunction "2_2") (pintype "passive"))
    )
    (net (code "52") (name "Net-(U1-EN)") (class "Default")
      (node (ref "R3") (pin "2") (pinfunction "2_2") (pintype "passive"))
      (node (ref "R6") (pin "2") (pinfunction "2_2") (pintype "passive"))
      (node (ref "U1") (pin "4") (pinfunction "EN_4") (pintype "input"))
    )
    (net (code "53") (name "Net-(U1-SW)") (class "Default")
      (node (ref "D1") (pin "A") (pinfunction "A_A") (pintype "passive"))
      (node (ref "L1") (pin "2") (pinfunction "2_2") (pintype "passive"))
      (node (ref "U1") (pin "1") (pinfunction "SW_1") (pintype "bidirectional"))
    )
    (net (code "54") (name "Net-(U3-FB)") (class "Default")
      (node (ref "R11") (pin "1") (pinfunction "1_1") (pintype "passive"))
      (node (ref "U3") (pin "3") (pinfunction "FB_3") (pintype "bidirectional"))
    )
    (net (code "55") (name "Net-(U3-SW)") (class "Default")
      (node (ref "C11") (pin "2") (pinfunction "2_2") (pintype "passive"))
      (node (ref "C4") (pin "2") (pinfunction "2_2") (pintype "passive"))
      (node (ref "D6") (pin "A") (pinfunction "A_A") (pintype "passive"))
      (node (ref "L2") (pin "2") (pinfunction "2_2") (pintype "passive"))
      (node (ref "U3") (pin "1") (pinfunction "SW_1") (pintype "bidirectional"))
    )
    (net (code "56") (name "VDD33") (class "Default")
      (node (ref "C10") (pin "2") (pinfunction "2_2") (pintype "passive"))
      (node (ref "C22") (pin "2") (pinfunction "2_2") (pintype "passive"))
      (node (ref "C23") (pin "2") (pinfunction "2_2") (pintype "passive"))
      (node (ref "C29") (pin "2") (pinfunction "2_2") (pintype "passive"))
      (node (ref "C7") (pin "2") (pinfunction "2_2") (pintype "passive"))
      (node (ref "J2") (pin "7") (pinfunction "7_7") (pintype "passive"))
      (node (ref "J3") (pin "3") (pinfunction "3_3") (pintype "passive"))
      (node (ref "J3") (pin "4") (pinfunction "4_4") (pintype "passive"))
      (node (ref "J5") (pin "3") (pinfunction "3_3") (pintype "passive"))
      (node (ref "J5") (pin "4") (pinfunction "4_4") (pintype "passive"))
      (node (ref "J6") (pin "5") (pinfunction "5_5") (pintype "passive"))
      (node (ref "R10") (pin "2") (pinfunction "2_2") (pintype "passive"))
      (node (ref "R16") (pin "1") (pinfunction "1_1") (pintype "passive"))
      (node (ref "R17") (pin "1") (pinfunction "1_1") (pintype "passive"))
      (node (ref "R24") (pin "1") (pinfunction "1_1") (pintype "passive"))
      (node (ref "R29") (pin "1") (pinfunction "1_1") (pintype "passive"))
      (node (ref "R30") (pin "1") (pinfunction "1_1") (pintype "passive"))
      (node (ref "R33") (pin "1") (pinfunction "1_1") (pintype "passive"))
      (node (ref "R4") (pin "2") (pinfunction "2_2") (pintype "passive"))
      (node (ref "R9") (pin "2") (pinfunction "2_2") (pintype "passive"))
      (node (ref "TEST7") (pin "1") (pinfunction "1_1") (pintype "passive"))
      (node (ref "U2") (pin "2") (pinfunction "Vout_2") (pintype "passive"))
    )
    (net (code "57") (name "VGH") (class "Default")
      (node (ref "C5") (pin "2") (pinfunction "2_2") (pintype "passive"))
      (node (ref "C8") (pin "2") (pinfunction "2_2") (pintype "passive"))
      (node (ref "D3") (pin "K") (pinfunction "K_K") (pintype "passive"))
      (node (ref "J2") (pin "41") (pinfunction "41_41") (pintype "passive"))
      (node (ref "R15") (pin "2") (pinfunction "2_2") (pintype "passive"))
      (node (ref "TEST4") (pin "1") (pinfunction "1_1") (pintype "passive"))
    )
    (net (code "58") (name "VGL") (class "Default")
      (node (ref "C12") (pin "2") (pinfunction "2_2") (pintype "passive"))
      (node (ref "C14") (pin "2") (pinfunction "2_2") (pintype "passive"))
      (node (ref "D4") (pin "A") (pinfunction "A_A") (pintype "passive"))
      (node (ref "J2") (pin "42") (pinfunction "42_42") (pintype "passive"))
      (node (ref "R21") (pin "2") (pinfunction "2_2") (pintype "passive"))
      (node (ref "TEST5") (pin "1") (pinfunction "1_1") (pintype "passive"))
    )
    (net (code "59") (name "unconnected-(J2-Pad45)") (class "Default")
      (node (ref "J2") (pin "45") (pinfunction "45_45") (pintype "passive"))
    )
    (net (code "60") (name "unconnected-(J2-Pad49)") (class "Default")
      (node (ref "J2") (pin "49") (pinfunction "49_49") (pintype "passive"))
    )
    (net (code "61") (name "unconnected-(J2-Pad50)") (class "Default")
      (node (ref "J2") (pin "50") (pinfunction "50_50") (pintype "passive"))
    )
    (net (code "62") (name "unconnected-(J2-Pad51)") (class "Default")
      (node (ref "J2") (pin "51") (pinfunction "51_51") (pintype "passive"))
    )
    (net (code "63") (name "unconnected-(J2-Pad52)") (class "Default")
      (node (ref "J2") (pin "52") (pinfunction "52_52") (pintype "passive"))
    )
    (net (code "64") (name "unconnected-(J3-Pad34)") (class "Default")
      (node (ref "J3") (pin "34") (pinfunction "34_34") (pintype "passive"))
    )
    (net (code "65") (name "unconnected-(J3-Pad45)") (class "Default")
      (node (ref "J3") (pin "45") (pinfunction "45_45") (pintype "passive"))
    )
    (net (code "66") (name "unconnected-(J3-Pad46)") (class "Default")
      (node (ref "J3") (pin "46") (pinfunction "46_46") (pintype "passive"))
    )
    (net (code "67") (name "unconnected-(J3-Pad47)") (class "Default")
      (node (ref "J3") (pin "47") (pinfunction "47_47") (pintype "passive"))
    )
    (net (code "68") (name "unconnected-(J3-Pad48)") (class "Default")
      (node (ref "J3") (pin "48") (pinfunction "48_48") (pintype "passive"))
    )
    (net (code "69") (name "unconnected-(J3-Pad51)") (class "Default")
      (node (ref "J3") (pin "51") (pinfunction "51_51") (pintype "passive"))
    )
    (net (code "70") (name "unconnected-(J3-Pad52)") (class "Default")
      (node (ref "J3") (pin "52") (pinfunction "52_52") (pintype "passive"))
    )
    (net (code "71") (name "unconnected-(J4-Pad37)") (class "Default")
      (node (ref "J4") (pin "37") (pinfunction "37_37") (pintype "passive"))
    )
  )
)
